# S7CAS-PLEIADES-CARTE-MERE_P07_FPGA_2.net
KiCad netlist of a schematic drawn in Altium Designer
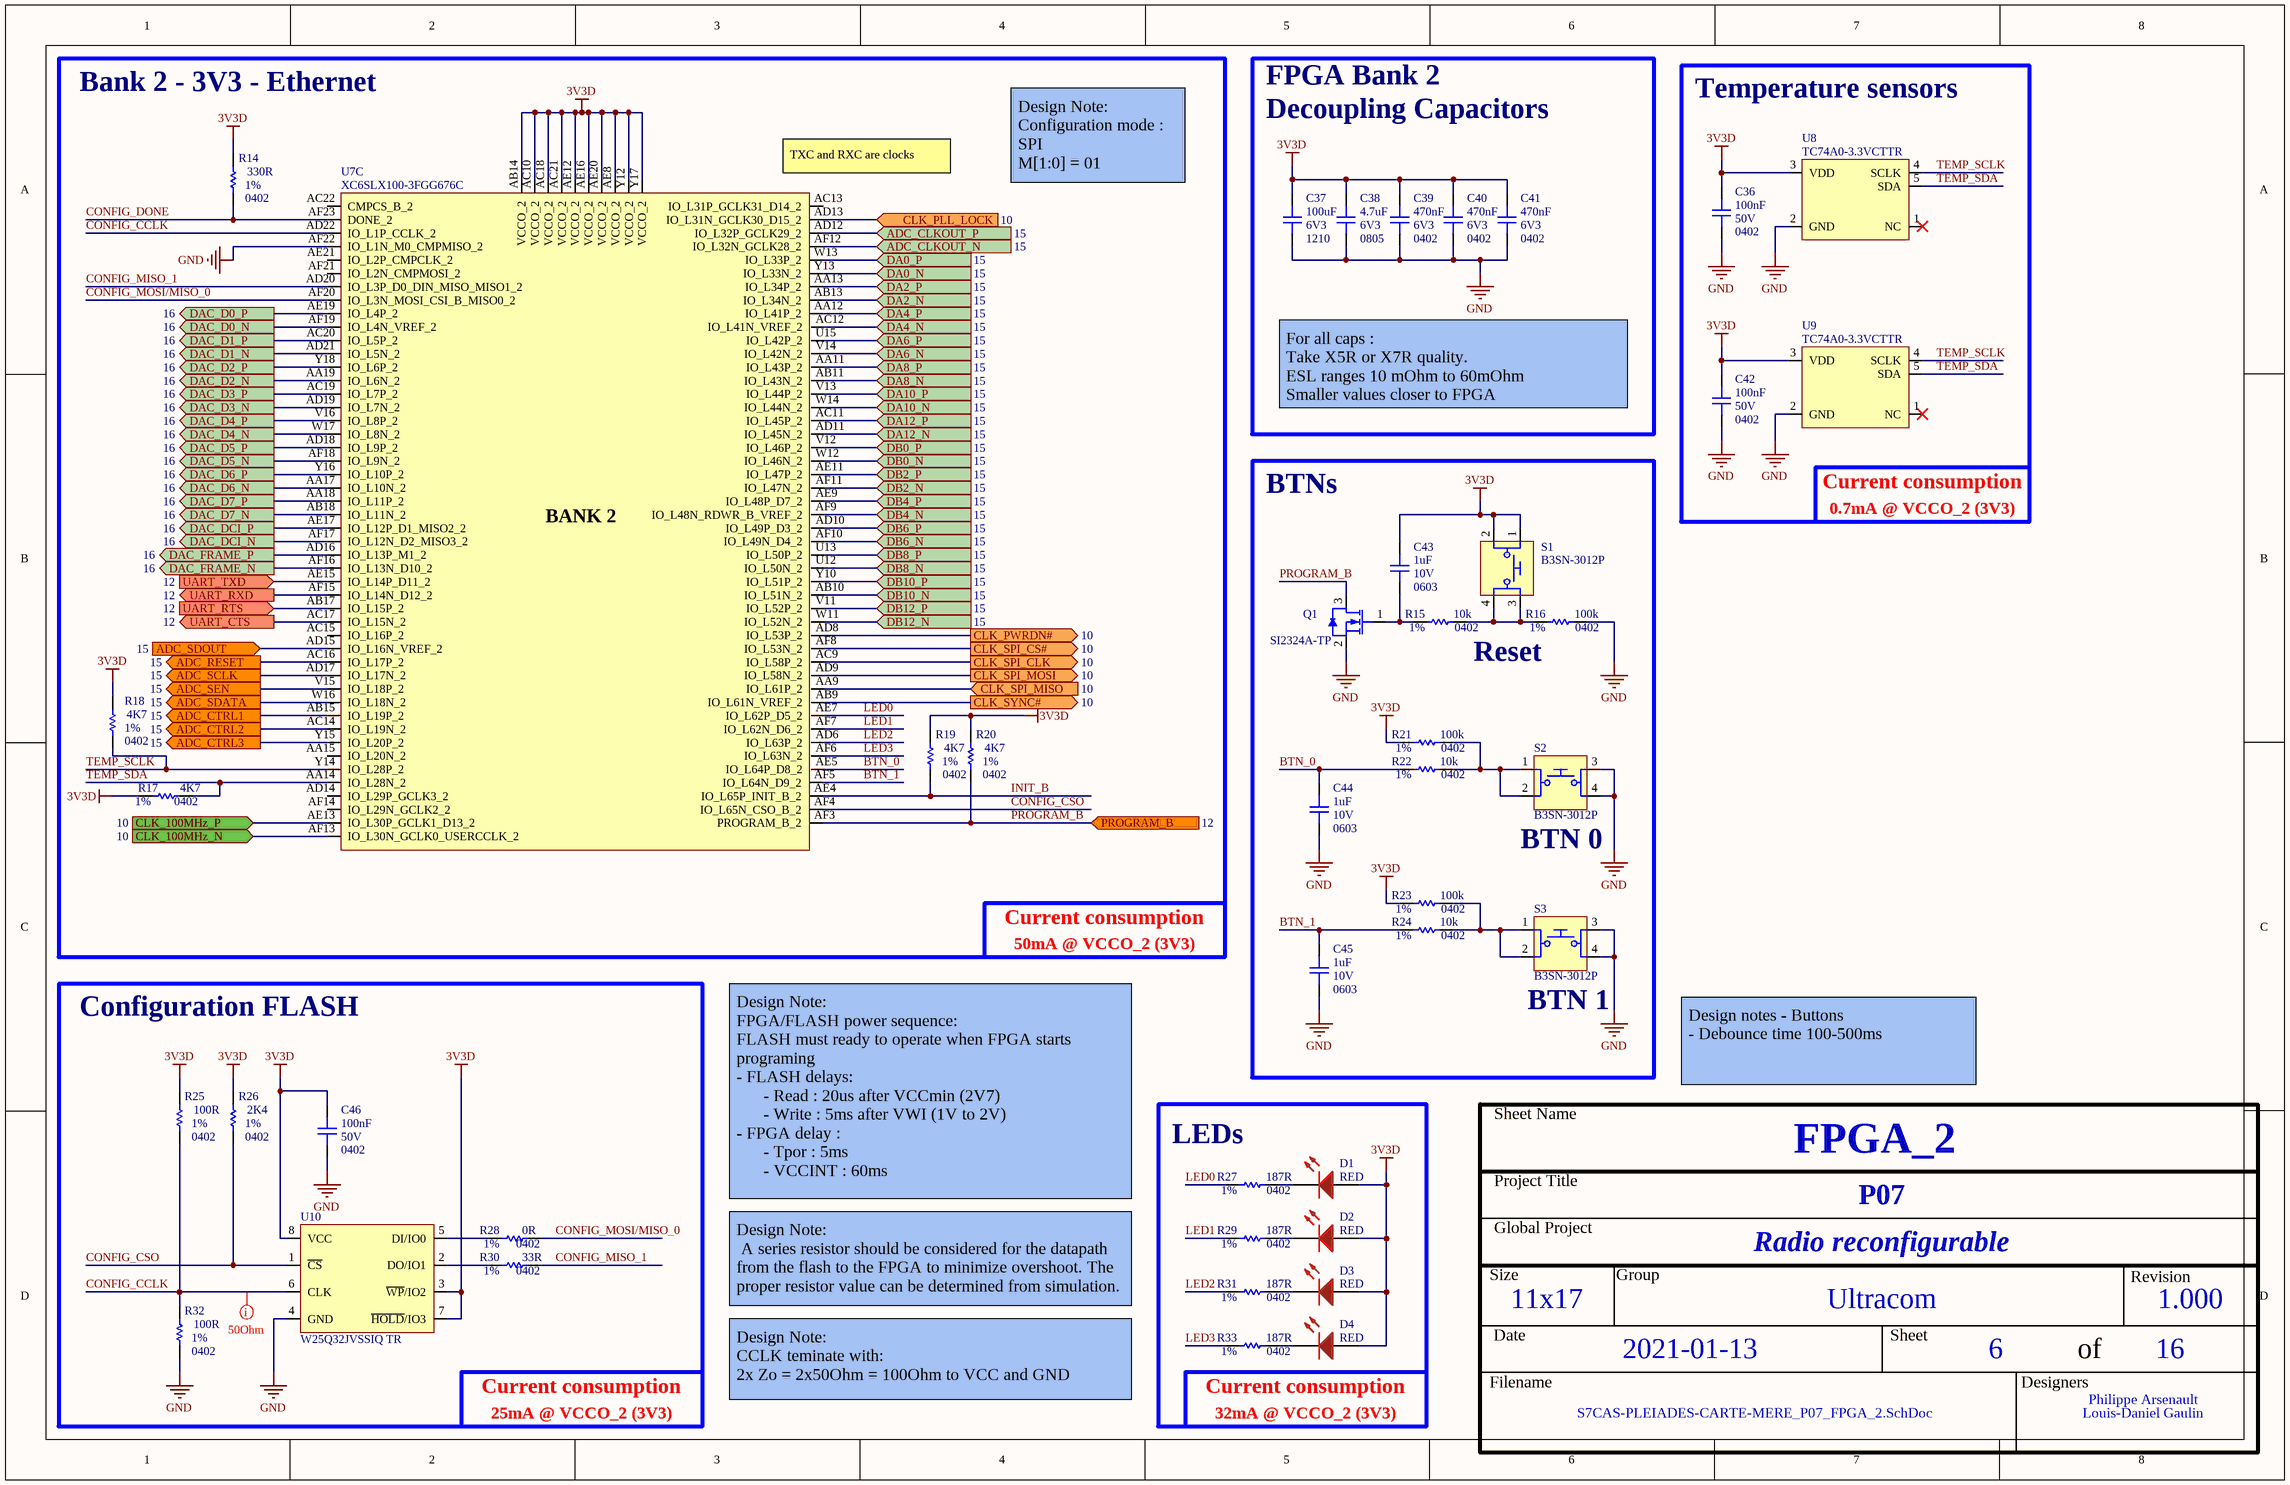
[diagram p0: S7CAS-PLEIADES-CARTE-MERE_P07_FPGA_2.SchDoc]

(export (version "E")
  (design (tool "Eeschema 10.0.6"))
  (components
    (comp (ref "C36")
      (value "100nF")
      (footprint "CAP_0402")
      (description "CAP - 0402")
      (fields
        (field (name "VOLTAGE") "50V")
        (field (name "PACKAGE") "0402")
        (field (name "CREATEDBY") "Jonathan Bouchard")
      )
      (libsource (lib "S7CAS_LIB2021") (part "CAP - 0402"))
    )
    (comp (ref "C37")
      (value "100uF")
      (footprint "CAP_1210")
      (description "CAP - 1210")
      (fields
        (field (name "VOLTAGE") "6V3")
        (field (name "PACKAGE") "1210")
        (field (name "CREATEDBY") "Jonathan Bouchard")
      )
      (libsource (lib "S7CAS_LIB2021") (part "CAP - 1210"))
    )
    (comp (ref "C38")
      (value "4.7uF")
      (footprint "CAP_0805")
      (description "CAP - 0805")
      (fields
        (field (name "VOLTAGE") "6V3")
        (field (name "PACKAGE") "0805")
        (field (name "CREATEDBY") "Jonathan Bouchard")
      )
      (libsource (lib "S7CAS_LIB2021") (part "CAP - 0805"))
    )
    (comp (ref "C39")
      (value "470nF")
      (footprint "CAP_0402")
      (description "CAP - 0402")
      (fields
        (field (name "VOLTAGE") "6V3")
        (field (name "PACKAGE") "0402")
        (field (name "CREATEDBY") "Jonathan Bouchard")
      )
      (libsource (lib "S7CAS_LIB2021") (part "CAP - 0402"))
    )
    (comp (ref "C40")
      (value "470nF")
      (footprint "CAP_0402")
      (description "CAP - 0402")
      (fields
        (field (name "VOLTAGE") "6V3")
        (field (name "PACKAGE") "0402")
        (field (name "CREATEDBY") "Jonathan Bouchard")
      )
      (libsource (lib "S7CAS_LIB2021") (part "CAP - 0402"))
    )
    (comp (ref "C41")
      (value "470nF")
      (footprint "CAP_0402")
      (description "CAP - 0402")
      (fields
        (field (name "VOLTAGE") "6V3")
        (field (name "PACKAGE") "0402")
        (field (name "CREATEDBY") "Jonathan Bouchard")
      )
      (libsource (lib "S7CAS_LIB2021") (part "CAP - 0402"))
    )
    (comp (ref "C42")
      (value "100nF")
      (footprint "CAP_0402")
      (description "CAP - 0402")
      (fields
        (field (name "VOLTAGE") "50V")
        (field (name "PACKAGE") "0402")
        (field (name "CREATEDBY") "Jonathan Bouchard")
      )
      (libsource (lib "S7CAS_LIB2021") (part "CAP - 0402"))
    )
    (comp (ref "C43")
      (value "1uF")
      (footprint "CAP_0603")
      (description "CAP - 0603")
      (fields
        (field (name "VOLTAGE") "10V")
        (field (name "PACKAGE") "0603")
        (field (name "CREATEDBY") "Jonathan Bouchard")
      )
      (libsource (lib "S7CAS_LIB2021") (part "CAP - 0603"))
    )
    (comp (ref "C44")
      (value "1uF")
      (footprint "CAP_0603")
      (description "CAP - 0603")
      (fields
        (field (name "VOLTAGE") "10V")
        (field (name "PACKAGE") "0603")
        (field (name "CREATEDBY") "Jonathan Bouchard")
      )
      (libsource (lib "S7CAS_LIB2021") (part "CAP - 0603"))
    )
    (comp (ref "C45")
      (value "1uF")
      (footprint "CAP_0603")
      (description "CAP - 0603")
      (fields
        (field (name "VOLTAGE") "10V")
        (field (name "PACKAGE") "0603")
        (field (name "CREATEDBY") "Jonathan Bouchard")
      )
      (libsource (lib "S7CAS_LIB2021") (part "CAP - 0603"))
    )
    (comp (ref "C46")
      (value "100nF")
      (footprint "CAP_0402")
      (description "CAP - 0402")
      (fields
        (field (name "VOLTAGE") "50V")
        (field (name "PACKAGE") "0402")
        (field (name "CREATEDBY") "Jonathan Bouchard")
      )
      (libsource (lib "S7CAS_LIB2021") (part "CAP - 0402"))
    )
    (comp (ref "D1")
      (value "RED")
      (footprint "LED_0603")
      (description "LED - 620nM RED 2mA - 0603")
      (fields
        (field (name "VOLTAGE") "1.8V")
        (field (name "MFG") "ROHM Semiconductor")
        (field (name "CREATEDBY") "Jonathan Bouchard")
      )
      (libsource (lib "S7CAS_LIB2021") (part "LED_SML-311UTT86"))
    )
    (comp (ref "D2")
      (value "RED")
      (footprint "LED_0603")
      (description "LED - 620nM RED 2mA - 0603")
      (fields
        (field (name "VOLTAGE") "1.8V")
        (field (name "MFG") "ROHM Semiconductor")
        (field (name "CREATEDBY") "Jonathan Bouchard")
      )
      (libsource (lib "S7CAS_LIB2021") (part "LED_SML-311UTT86"))
    )
    (comp (ref "D3")
      (value "RED")
      (footprint "LED_0603")
      (description "LED - 620nM RED 2mA - 0603")
      (fields
        (field (name "VOLTAGE") "1.8V")
        (field (name "MFG") "ROHM Semiconductor")
        (field (name "CREATEDBY") "Jonathan Bouchard")
      )
      (libsource (lib "S7CAS_LIB2021") (part "LED_SML-311UTT86"))
    )
    (comp (ref "D4")
      (value "RED")
      (footprint "LED_0603")
      (description "LED - 620nM RED 2mA - 0603")
      (fields
        (field (name "VOLTAGE") "1.8V")
        (field (name "MFG") "ROHM Semiconductor")
        (field (name "CREATEDBY") "Jonathan Bouchard")
      )
      (libsource (lib "S7CAS_LIB2021") (part "LED_SML-311UTT86"))
    )
    (comp (ref "Q1")
      (value "SI2324A-TP")
      (footprint "TRX_NMOS_SI324A-TP")
      (description "TRX - MOSFET N-CH 100V 2A - SOT-23")
      (fields (field (name "CREATEDBY/DATE") "*") (field (name "VERIFIEDBY") "*"))
      (libsource (lib "S7CAS_P07") (part "TRX_NMOS_SI2324A-TP"))
    )
    (comp (ref "R14")
      (value "330R")
      (footprint "RES_0402")
      (description "RES - 0402")
      (fields
        (field (name "VOLTAGE") "50V")
        (field (name "POWER") "1/16W")
        (field (name "PACKAGE") "0402")
        (field (name "PRECISION") "1%")
        (field (name "CREATEDBY") "Jonathan Bouchard")
      )
      (libsource (lib "S7CAS_LIB2021") (part "RES - 0402"))
    )
    (comp (ref "R15")
      (value "10k")
      (footprint "RES_0402")
      (description "RES - 0402")
      (fields
        (field (name "VOLTAGE") "50V")
        (field (name "POWER") "1/16W")
        (field (name "PACKAGE") "0402")
        (field (name "PRECISION") "1%")
        (field (name "CREATEDBY") "Jonathan Bouchard")
      )
      (libsource (lib "S7CAS_LIB2021") (part "RES - 0402"))
    )
    (comp (ref "R16")
      (value "100k")
      (footprint "RES_0402")
      (description "RES - 0402")
      (fields
        (field (name "VOLTAGE") "50V")
        (field (name "POWER") "1/16W")
        (field (name "PACKAGE") "0402")
        (field (name "PRECISION") "1%")
        (field (name "CREATEDBY") "Jonathan Bouchard")
      )
      (libsource (lib "S7CAS_LIB2021") (part "RES - 0402"))
    )
    (comp (ref "R17")
      (value "4K7")
      (footprint "RES_0402")
      (description "RES - 0402")
      (fields
        (field (name "VOLTAGE") "50V")
        (field (name "POWER") "1/16W")
        (field (name "PACKAGE") "0402")
        (field (name "PRECISION") "1%")
        (field (name "CREATEDBY") "Jonathan Bouchard")
      )
      (libsource (lib "S7CAS_LIB2021") (part "RES - 0402"))
    )
    (comp (ref "R18")
      (value "4K7")
      (footprint "RES_0402")
      (description "RES - 0402")
      (fields
        (field (name "VOLTAGE") "50V")
        (field (name "POWER") "1/16W")
        (field (name "PACKAGE") "0402")
        (field (name "PRECISION") "1%")
        (field (name "CREATEDBY") "Jonathan Bouchard")
      )
      (libsource (lib "S7CAS_LIB2021") (part "RES - 0402"))
    )
    (comp (ref "R19")
      (value "4K7")
      (footprint "RES_0402")
      (description "RES - 0402")
      (fields
        (field (name "VOLTAGE") "50V")
        (field (name "POWER") "1/16W")
        (field (name "PACKAGE") "0402")
        (field (name "PRECISION") "1%")
        (field (name "CREATEDBY") "Jonathan Bouchard")
      )
      (libsource (lib "S7CAS_LIB2021") (part "RES - 0402"))
    )
    (comp (ref "R20")
      (value "4K7")
      (footprint "RES_0402")
      (description "RES - 0402")
      (fields
        (field (name "VOLTAGE") "50V")
        (field (name "POWER") "1/16W")
        (field (name "PACKAGE") "0402")
        (field (name "PRECISION") "1%")
        (field (name "CREATEDBY") "Jonathan Bouchard")
      )
      (libsource (lib "S7CAS_LIB2021") (part "RES - 0402"))
    )
    (comp (ref "R21")
      (value "100k")
      (footprint "RES_0402")
      (description "RES - 0402")
      (fields
        (field (name "VOLTAGE") "50V")
        (field (name "POWER") "1/16W")
        (field (name "PACKAGE") "0402")
        (field (name "PRECISION") "1%")
        (field (name "CREATEDBY") "Jonathan Bouchard")
      )
      (libsource (lib "S7CAS_LIB2021") (part "RES - 0402"))
    )
    (comp (ref "R22")
      (value "10k")
      (footprint "RES_0402")
      (description "RES - 0402")
      (fields
        (field (name "VOLTAGE") "50V")
        (field (name "POWER") "1/16W")
        (field (name "PACKAGE") "0402")
        (field (name "PRECISION") "1%")
        (field (name "CREATEDBY") "Jonathan Bouchard")
      )
      (libsource (lib "S7CAS_LIB2021") (part "RES - 0402"))
    )
    (comp (ref "R23")
      (value "100k")
      (footprint "RES_0402")
      (description "RES - 0402")
      (fields
        (field (name "VOLTAGE") "50V")
        (field (name "POWER") "1/16W")
        (field (name "PACKAGE") "0402")
        (field (name "PRECISION") "1%")
        (field (name "CREATEDBY") "Jonathan Bouchard")
      )
      (libsource (lib "S7CAS_LIB2021") (part "RES - 0402"))
    )
    (comp (ref "R24")
      (value "10k")
      (footprint "RES_0402")
      (description "RES - 0402")
      (fields
        (field (name "VOLTAGE") "50V")
        (field (name "POWER") "1/16W")
        (field (name "PACKAGE") "0402")
        (field (name "PRECISION") "1%")
        (field (name "CREATEDBY") "Jonathan Bouchard")
      )
      (libsource (lib "S7CAS_LIB2021") (part "RES - 0402"))
    )
    (comp (ref "R25")
      (value "100R")
      (footprint "RES_0402")
      (description "RES - 0402")
      (fields
        (field (name "VOLTAGE") "50V")
        (field (name "POWER") "1/16W")
        (field (name "PACKAGE") "0402")
        (field (name "PRECISION") "1%")
        (field (name "CREATEDBY") "Jonathan Bouchard")
      )
      (libsource (lib "S7CAS_LIB2021") (part "RES - 0402"))
    )
    (comp (ref "R26")
      (value "2K4")
      (footprint "RES_0402")
      (description "RES - 0402")
      (fields
        (field (name "VOLTAGE") "50V")
        (field (name "POWER") "1/16W")
        (field (name "PACKAGE") "0402")
        (field (name "PRECISION") "1%")
        (field (name "CREATEDBY") "Jonathan Bouchard")
      )
      (libsource (lib "S7CAS_LIB2021") (part "RES - 0402"))
    )
    (comp (ref "R27")
      (value "187R")
      (footprint "RES_0402")
      (description "RES - 0402")
      (fields
        (field (name "VOLTAGE") "50V")
        (field (name "POWER") "1/16W")
        (field (name "PACKAGE") "0402")
        (field (name "PRECISION") "1%")
        (field (name "CREATEDBY") "Jonathan Bouchard")
      )
      (libsource (lib "S7CAS_LIB2021") (part "RES - 0402"))
    )
    (comp (ref "R28")
      (value "0R")
      (footprint "RES_0402")
      (description "RES - 0402")
      (fields
        (field (name "VOLTAGE") "50V")
        (field (name "POWER") "1/16W")
        (field (name "PACKAGE") "0402")
        (field (name "PRECISION") "1%")
        (field (name "CREATEDBY") "Jonathan Bouchard")
      )
      (libsource (lib "S7CAS_LIB2021") (part "RES - 0402"))
    )
    (comp (ref "R29")
      (value "187R")
      (footprint "RES_0402")
      (description "RES - 0402")
      (fields
        (field (name "VOLTAGE") "50V")
        (field (name "POWER") "1/16W")
        (field (name "PACKAGE") "0402")
        (field (name "PRECISION") "1%")
        (field (name "CREATEDBY") "Jonathan Bouchard")
      )
      (libsource (lib "S7CAS_LIB2021") (part "RES - 0402"))
    )
    (comp (ref "R30")
      (value "33R")
      (footprint "RES_0402")
      (description "RES - 0402")
      (fields
        (field (name "VOLTAGE") "50V")
        (field (name "POWER") "1/16W")
        (field (name "PACKAGE") "0402")
        (field (name "PRECISION") "1%")
        (field (name "CREATEDBY") "Jonathan Bouchard")
      )
      (libsource (lib "S7CAS_LIB2021") (part "RES - 0402"))
    )
    (comp (ref "R31")
      (value "187R")
      (footprint "RES_0402")
      (description "RES - 0402")
      (fields
        (field (name "VOLTAGE") "50V")
        (field (name "POWER") "1/16W")
        (field (name "PACKAGE") "0402")
        (field (name "PRECISION") "1%")
        (field (name "CREATEDBY") "Jonathan Bouchard")
      )
      (libsource (lib "S7CAS_LIB2021") (part "RES - 0402"))
    )
    (comp (ref "R32")
      (value "100R")
      (footprint "RES_0402")
      (description "RES - 0402")
      (fields
        (field (name "VOLTAGE") "50V")
        (field (name "POWER") "1/16W")
        (field (name "PACKAGE") "0402")
        (field (name "PRECISION") "1%")
        (field (name "CREATEDBY") "Jonathan Bouchard")
      )
      (libsource (lib "S7CAS_LIB2021") (part "RES - 0402"))
    )
    (comp (ref "R33")
      (value "187R")
      (footprint "RES_0402")
      (description "RES - 0402")
      (fields
        (field (name "VOLTAGE") "50V")
        (field (name "POWER") "1/16W")
        (field (name "PACKAGE") "0402")
        (field (name "PRECISION") "1%")
        (field (name "CREATEDBY") "Jonathan Bouchard")
      )
      (libsource (lib "S7CAS_LIB2021") (part "RES - 0402"))
    )
    (comp (ref "S1")
      (value "B3SN-3012P")
      (footprint "SWI_TACT_B3SN-3012P")
      (description "SWI - SWITCH TACTILE SPST-NO 0.05A 24V -SMD")
      (fields
        (field (name "CREATEDBY/DATE") "Olivier Bernard / 5/12/2017")
        (field (name "VERIFIEDBY") "Caroline Paulin / 11 juillet 2018")
      )
      (libsource (lib "") (part "SWI_TACT_B3SN-3012P_1_1"))
    )
    (comp (ref "S2")
      (value "B3SN-3012P")
      (footprint "SWI_TACT_B3SN-3012P")
      (description "SWI - SWITCH TACTILE SPST-NO 0.05A 24V -SMD")
      (fields
        (field (name "CREATEDBY/DATE") "Olivier Bernard / 5/12/2017")
        (field (name "VERIFIEDBY") "Caroline Paulin / 11 juillet 2018")
      )
      (libsource (lib "S7CAS_LIB2021") (part "SWI_TACT_B3SN-3012P_1"))
    )
    (comp (ref "S3")
      (value "B3SN-3012P")
      (footprint "SWI_TACT_B3SN-3012P")
      (description "SWI - SWITCH TACTILE SPST-NO 0.05A 24V -SMD")
      (fields
        (field (name "CREATEDBY/DATE") "Olivier Bernard / 5/12/2017")
        (field (name "VERIFIEDBY") "Caroline Paulin / 11 juillet 2018")
      )
      (libsource (lib "S7CAS_LIB2021") (part "SWI_TACT_B3SN-3012P_1"))
    )
    (comp (ref "U7")
      (value "XC6SLX100-3FGG676C")
      (footprint "FPGA_XILINX_FGG676")
      (description "FPGA - XILINX SPARTAN 6 480 I/O - BGA-676")
      (fields
        (field (name "VOLTAGE") "1.14 V ~ 1.26 V")
        (field (name "MFG") "Xilinx")
        (field (name "CREATEDBY") "Jonathan Bouchard")
      )
      (libsource (lib "S7CAS_LIB2021") (part "FPGA_XC6SLX100-3FGG676C"))
    )
    (comp (ref "U8")
      (value "TC74A0-3.3VCTTR")
      (footprint "SEN_TEMP_TC74A0-3.3VCTTR")
      (description "SENS - TEMPERATURE SENSOR I2C/SMBUS - SOT23-5")
      (fields
        (field (name "VOLTAGE") "2.7 V ~ 5.5 V")
        (field (name "MFG") "Microchip")
        (field (name "CREATEDBY") "Jonathan Bouchard")
      )
      (libsource (lib "S7CAS_LIB2021") (part "SENS_TEMP_TC74A0-3.3VCTTR"))
    )
    (comp (ref "U9")
      (value "TC74A0-3.3VCTTR")
      (footprint "SEN_TEMP_TC74A0-3.3VCTTR")
      (description "SENS - TEMPERATURE SENSOR I2C/SMBUS - SOT23-5")
      (fields
        (field (name "VOLTAGE") "2.7 V ~ 5.5 V")
        (field (name "MFG") "Microchip")
        (field (name "CREATEDBY") "Jonathan Bouchard")
      )
      (libsource (lib "S7CAS_LIB2021") (part "SENS_TEMP_TC74A0-3.3VCTTR"))
    )
    (comp (ref "U10")
      (value "W25Q32JVSSIQ TR")
      (footprint "MEM_FLASH_W25Q32JVSSIQ TR")
      (description "MEM - FLASH NOR 32Mb 133MHZ - 8-SOIC")
      (fields
        (field (name "VOLTAGE") "2.7 V ~ 3.6 V")
        (field (name "MFG") "Winbond Electronics")
        (field (name "CREATEDBY") "Louis-Daniel Gaulin")
      )
      (libsource (lib "S7CAS_P07") (part "MEM_FLASH_W25Q32JVSSIQ TR"))
    )
  )
  (nets
    (net (code "1") (name "/ADC_CLKOUT_N") (class "Default")
      (node (ref "U7") (pin "AF12") (pinfunction "IO_L32N_GCLK28_2_AF12") (pintype "passive"))
    )
    (net (code "2") (name "/ADC_CLKOUT_P") (class "Default")
      (node (ref "U7") (pin "AD12") (pinfunction "IO_L32P_GCLK29_2_AD12") (pintype "passive"))
    )
    (net (code "3") (name "/ADC_CTRL1") (class "Default")
      (node (ref "U7") (pin "AB15") (pinfunction "IO_L19P_2_AB15") (pintype "passive"))
    )
    (net (code "4") (name "/ADC_CTRL2") (class "Default")
      (node (ref "U7") (pin "AC14") (pinfunction "IO_L19N_2_AC14") (pintype "passive"))
    )
    (net (code "5") (name "/ADC_CTRL3") (class "Default")
      (node (ref "U7") (pin "Y15") (pinfunction "IO_L20P_2_Y15") (pintype "passive"))
    )
    (net (code "6") (name "/ADC_RESET") (class "Default")
      (node (ref "U7") (pin "AC16") (pinfunction "IO_L17P_2_AC16") (pintype "passive"))
    )
    (net (code "7") (name "/ADC_SCLK") (class "Default")
      (node (ref "U7") (pin "AD17") (pinfunction "IO_L17N_2_AD17") (pintype "passive"))
    )
    (net (code "8") (name "/ADC_SDATA") (class "Default")
      (node (ref "U7") (pin "W16") (pinfunction "IO_L18N_2_W16") (pintype "passive"))
    )
    (net (code "9") (name "/ADC_SDOUT") (class "Default")
      (node (ref "U7") (pin "AD15") (pinfunction "IO_L16N_VREF_2_AD15") (pintype "passive"))
    )
    (net (code "10") (name "/ADC_SEN") (class "Default")
      (node (ref "U7") (pin "V15") (pinfunction "IO_L18P_2_V15") (pintype "passive"))
    )
    (net (code "11") (name "/BTN_0") (class "Default")
      (node (ref "C44") (pin "2") (pinfunction "2_2") (pintype "passive"))
      (node (ref "R22") (pin "1") (pinfunction "1_1") (pintype "passive"))
      (node (ref "U7") (pin "AE5") (pinfunction "IO_L64P_D8_2_AE5") (pintype "passive"))
    )
    (net (code "12") (name "/BTN_1") (class "Default")
      (node (ref "C45") (pin "2") (pinfunction "2_2") (pintype "passive"))
      (node (ref "R24") (pin "1") (pinfunction "1_1") (pintype "passive"))
      (node (ref "U7") (pin "AF5") (pinfunction "IO_L64N_D9_2_AF5") (pintype "passive"))
    )
    (net (code "13") (name "/CLK_100MHz_N") (class "Default")
      (node (ref "U7") (pin "AF13") (pinfunction "IO_L30N_GCLK0_USERCCLK_2_AF13") (pintype "passive"))
    )
    (net (code "14") (name "/CLK_100MHz_P") (class "Default")
      (node (ref "U7") (pin "AE13") (pinfunction "IO_L30P_GCLK1_D13_2_AE13") (pintype "passive"))
    )
    (net (code "15") (name "/CLK_PLL_LOCK") (class "Default")
      (node (ref "U7") (pin "AD13") (pinfunction "IO_L31N_GCLK30_D15_2_AD13") (pintype "passive"))
    )
    (net (code "16") (name "/CLK_PWRDN#") (class "Default")
      (node (ref "U7") (pin "AD8") (pinfunction "IO_L53P_2_AD8") (pintype "passive"))
    )
    (net (code "17") (name "/CLK_SPI_CLK") (class "Default")
      (node (ref "U7") (pin "AC9") (pinfunction "IO_L58P_2_AC9") (pintype "passive"))
    )
    (net (code "18") (name "/CLK_SPI_CS#") (class "Default")
      (node (ref "U7") (pin "AF8") (pinfunction "IO_L53N_2_AF8") (pintype "passive"))
    )
    (net (code "19") (name "/CLK_SPI_MISO") (class "Default")
      (node (ref "U7") (pin "AA9") (pinfunction "IO_L61P_2_AA9") (pintype "passive"))
    )
    (net (code "20") (name "/CLK_SPI_MOSI") (class "Default")
      (node (ref "U7") (pin "AD9") (pinfunction "IO_L58N_2_AD9") (pintype "passive"))
    )
    (net (code "21") (name "/CLK_SYNC#") (class "Default")
      (node (ref "U7") (pin "AB9") (pinfunction "IO_L61N_VREF_2_AB9") (pintype "passive"))
    )
    (net (code "22") (name "/CONFIG_CCLK") (class "Default")
      (node (ref "R25") (pin "1") (pinfunction "1_1") (pintype "passive"))
      (node (ref "R32") (pin "2") (pinfunction "2_2") (pintype "passive"))
      (node (ref "U10") (pin "6") (pinfunction "CLK_6") (pintype "passive"))
      (node (ref "U7") (pin "AD22") (pinfunction "IO_L1P_CCLK_2_AD22") (pintype "passive"))
    )
    (net (code "23") (name "/CONFIG_CSO") (class "Default")
      (node (ref "R26") (pin "1") (pinfunction "1_1") (pintype "passive"))
      (node (ref "U10") (pin "1") (pinfunction "CS_1") (pintype "passive"))
      (node (ref "U7") (pin "AF4") (pinfunction "IO_L65N_CSO_B_2_AF4") (pintype "passive"))
    )
    (net (code "24") (name "/CONFIG_DONE") (class "Default")
      (node (ref "R14") (pin "1") (pinfunction "1_1") (pintype "passive"))
      (node (ref "U7") (pin "AF23") (pinfunction "DONE_2_AF23") (pintype "passive"))
    )
    (net (code "25") (name "/CONFIG_MISO_1") (class "Default")
      (node (ref "R30") (pin "1") (pinfunction "1_1") (pintype "passive"))
      (node (ref "U7") (pin "AD20") (pinfunction "IO_L3P_D0_DIN_MISO_MISO1_2_AD20") (pintype "passive"))
    )
    (net (code "26") (name "/CONFIG_MOSI{slash}MISO_0") (class "Default")
      (node (ref "R28") (pin "1") (pinfunction "1_1") (pintype "passive"))
      (node (ref "U7") (pin "AF20") (pinfunction "IO_L3N_MOSI_CSI_B_MISO0_2_AF20") (pintype "passive"))
    )
    (net (code "27") (name "/DA0_N") (class "Default")
      (node (ref "U7") (pin "Y13") (pinfunction "IO_L33N_2_Y13") (pintype "passive"))
    )
    (net (code "28") (name "/DA0_P") (class "Default")
      (node (ref "U7") (pin "W13") (pinfunction "IO_L33P_2_W13") (pintype "passive"))
    )
    (net (code "29") (name "/DA2_N") (class "Default")
      (node (ref "U7") (pin "AB13") (pinfunction "IO_L34N_2_AB13") (pintype "passive"))
    )
    (net (code "30") (name "/DA2_P") (class "Default")
      (node (ref "U7") (pin "AA13") (pinfunction "IO_L34P_2_AA13") (pintype "passive"))
    )
    (net (code "31") (name "/DA4_N") (class "Default")
      (node (ref "U7") (pin "AC12") (pinfunction "IO_L41N_VREF_2_AC12") (pintype "passive"))
    )
    (net (code "32") (name "/DA4_P") (class "Default")
      (node (ref "U7") (pin "AA12") (pinfunction "IO_L41P_2_AA12") (pintype "passive"))
    )
    (net (code "33") (name "/DA6_N") (class "Default")
      (node (ref "U7") (pin "V14") (pinfunction "IO_L42N_2_V14") (pintype "passive"))
    )
    (net (code "34") (name "/DA6_P") (class "Default")
      (node (ref "U7") (pin "U15") (pinfunction "IO_L42P_2_U15") (pintype "passive"))
    )
    (net (code "35") (name "/DA8_N") (class "Default")
      (node (ref "U7") (pin "AB11") (pinfunction "IO_L43N_2_AB11") (pintype "passive"))
    )
    (net (code "36") (name "/DA8_P") (class "Default")
      (node (ref "U7") (pin "AA11") (pinfunction "IO_L43P_2_AA11") (pintype "passive"))
    )
    (net (code "37") (name "/DA10_N") (class "Default")
      (node (ref "U7") (pin "W14") (pinfunction "IO_L44N_2_W14") (pintype "passive"))
    )
    (net (code "38") (name "/DA10_P") (class "Default")
      (node (ref "U7") (pin "V13") (pinfunction "IO_L44P_2_V13") (pintype "passive"))
    )
    (net (code "39") (name "/DA12_N") (class "Default")
      (node (ref "U7") (pin "AD11") (pinfunction "IO_L45N_2_AD11") (pintype "passive"))
    )
    (net (code "40") (name "/DA12_P") (class "Default")
      (node (ref "U7") (pin "AC11") (pinfunction "IO_L45P_2_AC11") (pintype "passive"))
    )
    (net (code "41") (name "/DAC_D0_N") (class "Default")
      (node (ref "U7") (pin "AF19") (pinfunction "IO_L4N_VREF_2_AF19") (pintype "passive"))
    )
    (net (code "42") (name "/DAC_D0_P") (class "Default")
      (node (ref "U7") (pin "AE19") (pinfunction "IO_L4P_2_AE19") (pintype "passive"))
    )
    (net (code "43") (name "/DAC_D1_N") (class "Default")
      (node (ref "U7") (pin "AD21") (pinfunction "IO_L5N_2_AD21") (pintype "passive"))
    )
    (net (code "44") (name "/DAC_D1_P") (class "Default")
      (node (ref "U7") (pin "AC20") (pinfunction "IO_L5P_2_AC20") (pintype "passive"))
    )
    (net (code "45") (name "/DAC_D2_N") (class "Default")
      (node (ref "U7") (pin "AA19") (pinfunction "IO_L6N_2_AA19") (pintype "passive"))
    )
    (net (code "46") (name "/DAC_D2_P") (class "Default")
      (node (ref "U7") (pin "Y18") (pinfunction "IO_L6P_2_Y18") (pintype "passive"))
    )
    (net (code "47") (name "/DAC_D3_N") (class "Default")
      (node (ref "U7") (pin "AD19") (pinfunction "IO_L7N_2_AD19") (pintype "passive"))
    )
    (net (code "48") (name "/DAC_D3_P") (class "Default")
      (node (ref "U7") (pin "AC19") (pinfunction "IO_L7P_2_AC19") (pintype "passive"))
    )
    (net (code "49") (name "/DAC_D4_N") (class "Default")
      (node (ref "U7") (pin "W17") (pinfunction "IO_L8N_2_W17") (pintype "passive"))
    )
    (net (code "50") (name "/DAC_D4_P") (class "Default")
      (node (ref "U7") (pin "V16") (pinfunction "IO_L8P_2_V16") (pintype "passive"))
    )
    (net (code "51") (name "/DAC_D5_N") (class "Default")
      (node (ref "U7") (pin "AF18") (pinfunction "IO_L9N_2_AF18") (pintype "passive"))
    )
    (net (code "52") (name "/DAC_D5_P") (class "Default")
      (node (ref "U7") (pin "AD18") (pinfunction "IO_L9P_2_AD18") (pintype "passive"))
    )
    (net (code "53") (name "/DAC_D6_N") (class "Default")
      (node (ref "U7") (pin "AA17") (pinfunction "IO_L10N_2_AA17") (pintype "passive"))
    )
    (net (code "54") (name "/DAC_D6_P") (class "Default")
      (node (ref "U7") (pin "Y16") (pinfunction "IO_L10P_2_Y16") (pintype "passive"))
    )
    (net (code "55") (name "/DAC_D7_N") (class "Default")
      (node (ref "U7") (pin "AB18") (pinfunction "IO_L11N_2_AB18") (pintype "passive"))
    )
    (net (code "56") (name "/DAC_D7_P") (class "Default")
      (node (ref "U7") (pin "AA18") (pinfunction "IO_L11P_2_AA18") (pintype "passive"))
    )
    (net (code "57") (name "/DAC_DCI_N") (class "Default")
      (node (ref "U7") (pin "AF17") (pinfunction "IO_L12N_D2_MISO3_2_AF17") (pintype "passive"))
    )
    (net (code "58") (name "/DAC_DCI_P") (class "Default")
      (node (ref "U7") (pin "AE17") (pinfunction "IO_L12P_D1_MISO2_2_AE17") (pintype "passive"))
    )
    (net (code "59") (name "/DAC_FRAME_N") (class "Default")
      (node (ref "U7") (pin "AF16") (pinfunction "IO_L13N_D10_2_AF16") (pintype "passive"))
    )
    (net (code "60") (name "/DAC_FRAME_P") (class "Default")
      (node (ref "U7") (pin "AD16") (pinfunction "IO_L13P_M1_2_AD16") (pintype "passive"))
    )
    (net (code "61") (name "/DB0_N") (class "Default")
      (node (ref "U7") (pin "W12") (pinfunction "IO_L46N_2_W12") (pintype "passive"))
    )
    (net (code "62") (name "/DB0_P") (class "Default")
      (node (ref "U7") (pin "V12") (pinfunction "IO_L46P_2_V12") (pintype "passive"))
    )
    (net (code "63") (name "/DB2_N") (class "Default")
      (node (ref "U7") (pin "AF11") (pinfunction "IO_L47N_2_AF11") (pintype "passive"))
    )
    (net (code "64") (name "/DB2_P") (class "Default")
      (node (ref "U7") (pin "AE11") (pinfunction "IO_L47P_2_AE11") (pintype "passive"))
    )
    (net (code "65") (name "/DB4_N") (class "Default")
      (node (ref "U7") (pin "AF9") (pinfunction "IO_L48N_RDWR_B_VREF_2_AF9") (pintype "passive"))
    )
    (net (code "66") (name "/DB4_P") (class "Default")
      (node (ref "U7") (pin "AE9") (pinfunction "IO_L48P_D7_2_AE9") (pintype "passive"))
    )
    (net (code "67") (name "/DB6_N") (class "Default")
      (node (ref "U7") (pin "AF10") (pinfunction "IO_L49N_D4_2_AF10") (pintype "passive"))
    )
    (net (code "68") (name "/DB6_P") (class "Default")
      (node (ref "U7") (pin "AD10") (pinfunction "IO_L49P_D3_2_AD10") (pintype "passive"))
    )
    (net (code "69") (name "/DB8_N") (class "Default")
      (node (ref "U7") (pin "U12") (pinfunction "IO_L50N_2_U12") (pintype "passive"))
    )
    (net (code "70") (name "/DB8_P") (class "Default")
      (node (ref "U7") (pin "U13") (pinfunction "IO_L50P_2_U13") (pintype "passive"))
    )
    (net (code "71") (name "/DB10_N") (class "Default")
      (node (ref "U7") (pin "AB10") (pinfunction "IO_L51N_2_AB10") (pintype "passive"))
    )
    (net (code "72") (name "/DB10_P") (class "Default")
      (node (ref "U7") (pin "Y10") (pinfunction "IO_L51P_2_Y10") (pintype "passive"))
    )
    (net (code "73") (name "/DB12_N") (class "Default")
      (node (ref "U7") (pin "W11") (pinfunction "IO_L52N_2_W11") (pintype "passive"))
    )
    (net (code "74") (name "/DB12_P") (class "Default")
      (node (ref "U7") (pin "V11") (pinfunction "IO_L52P_2_V11") (pintype "passive"))
    )
    (net (code "75") (name "/INIT_B") (class "Default")
      (node (ref "R19") (pin "1") (pinfunction "1_1") (pintype "passive"))
      (node (ref "U7") (pin "AE4") (pinfunction "IO_L65P_INIT_B_2_AE4") (pintype "passive"))
    )
    (net (code "76") (name "/LED0") (class "Default")
      (node (ref "R27") (pin "1") (pinfunction "1_1") (pintype "passive"))
      (node (ref "U7") (pin "AE7") (pinfunction "IO_L62P_D5_2_AE7") (pintype "passive"))
    )
    (net (code "77") (name "/LED1") (class "Default")
      (node (ref "R29") (pin "1") (pinfunction "1_1") (pintype "passive"))
      (node (ref "U7") (pin "AF7") (pinfunction "IO_L62N_D6_2_AF7") (pintype "passive"))
    )
    (net (code "78") (name "/LED2") (class "Default")
      (node (ref "R31") (pin "1") (pinfunction "1_1") (pintype "passive"))
      (node (ref "U7") (pin "AD6") (pinfunction "IO_L63P_2_AD6") (pintype "passive"))
    )
    (net (code "79") (name "/LED3") (class "Default")
      (node (ref "R33") (pin "1") (pinfunction "1_1") (pintype "passive"))
      (node (ref "U7") (pin "AF6") (pinfunction "IO_L63N_2_AF6") (pintype "passive"))
    )
    (net (code "80") (name "/PROGRAM_B") (class "Default")
      (node (ref "Q1") (pin "3") (pinfunction "D_3") (pintype "passive"))
      (node (ref "R20") (pin "1") (pinfunction "1_1") (pintype "passive"))
      (node (ref "U7") (pin "AF3") (pinfunction "PROGRAM_B_2_AF3") (pintype "passive"))
    )
    (net (code "81") (name "/TEMP_SCLK") (class "Default")
      (node (ref "R18") (pin "1") (pinfunction "1_1") (pintype "passive"))
      (node (ref "U7") (pin "Y14") (pinfunction "IO_L28P_2_Y14") (pintype "passive"))
      (node (ref "U8") (pin "4") (pinfunction "SCLK_4") (pintype "passive"))
      (node (ref "U9") (pin "4") (pinfunction "SCLK_4") (pintype "passive"))
    )
    (net (code "82") (name "/TEMP_SDA") (class "Default")
      (node (ref "R17") (pin "2") (pinfunction "2_2") (pintype "passive"))
      (node (ref "U7") (pin "AA14") (pinfunction "IO_L28N_2_AA14") (pintype "passive"))
      (node (ref "U8") (pin "5") (pinfunction "SDA_5") (pintype "passive"))
      (node (ref "U9") (pin "5") (pinfunction "SDA_5") (pintype "passive"))
    )
    (net (code "83") (name "/UART_CTS") (class "Default")
      (node (ref "U7") (pin "AC17") (pinfunction "IO_L15N_2_AC17") (pintype "passive"))
    )
    (net (code "84") (name "/UART_RTS") (class "Default")
      (node (ref "U7") (pin "AB17") (pinfunction "IO_L15P_2_AB17") (pintype "passive"))
    )
    (net (code "85") (name "/UART_RXD") (class "Default")
      (node (ref "U7") (pin "AF15") (pinfunction "IO_L14N_D12_2_AF15") (pintype "passive"))
    )
    (net (code "86") (name "/UART_TXD") (class "Default")
      (node (ref "U7") (pin "AE15") (pinfunction "IO_L14P_D11_2_AE15") (pintype "passive"))
    )
    (net (code "87") (name "3V3D") (class "Default")
      (node (ref "C36") (pin "2") (pinfunction "2_2") (pintype "passive"))
      (node (ref "C37") (pin "2") (pinfunction "2_2") (pintype "passive"))
      (node (ref "C38") (pin "2") (pinfunction "2_2") (pintype "passive"))
      (node (ref "C39") (pin "2") (pinfunction "2_2") (pintype "passive"))
      (node (ref "C40") (pin "2") (pinfunction "2_2") (pintype "passive"))
      (node (ref "C41") (pin "2") (pinfunction "2_2") (pintype "passive"))
      (node (ref "C42") (pin "2") (pinfunction "2_2") (pintype "passive"))
      (node (ref "C43") (pin "2") (pinfunction "2_2") (pintype "passive"))
      (node (ref "C46") (pin "2") (pinfunction "2_2") (pintype "passive"))
      (node (ref "D1") (pin "A") (pinfunction "A_A") (pintype "passive"))
      (node (ref "D2") (pin "A") (pinfunction "A_A") (pintype "passive"))
      (node (ref "D3") (pin "A") (pinfunction "A_A") (pintype "passive"))
      (node (ref "D4") (pin "A") (pinfunction "A_A") (pintype "passive"))
      (node (ref "R14") (pin "2") (pinfunction "2_2") (pintype "passive"))
      (node (ref "R17") (pin "1") (pinfunction "1_1") (pintype "passive"))
      (node (ref "R18") (pin "2") (pinfunction "2_2") (pintype "passive"))
      (node (ref "R19") (pin "2") (pinfunction "2_2") (pintype "passive"))
      (node (ref "R20") (pin "2") (pinfunction "2_2") (pintype "passive"))
      (node (ref "R21") (pin "1") (pinfunction "1_1") (pintype "passive"))
      (node (ref "R23") (pin "1") (pinfunction "1_1") (pintype "passive"))
      (node (ref "R25") (pin "2") (pinfunction "2_2") (pintype "passive"))
      (node (ref "R26") (pin "2") (pinfunction "2_2") (pintype "passive"))
      (node (ref "S1") (pin "1") (pinfunction "1_1") (pintype "passive"))
      (node (ref "S1") (pin "2") (pinfunction "2_2") (pintype "passive"))
      (node (ref "U10") (pin "3") (pinfunction "~{WP}/IO2_3") (pintype "passive"))
      (node (ref "U10") (pin "7") (pinfunction "~{HOLD}/IO3_7") (pintype "passive"))
      (node (ref "U10") (pin "8") (pinfunction "VCC_8") (pintype "passive"))
      (node (ref "U7") (pin "AB14") (pinfunction "VCCO_2_AB14") (pintype "passive"))
      (node (ref "U7") (pin "AC10") (pinfunction "VCCO_2_AC10") (pintype "passive"))
      (node (ref "U7") (pin "AC18") (pinfunction "VCCO_2_AC18") (pintype "passive"))
      (node (ref "U7") (pin "AC21") (pinfunction "VCCO_2_AC21") (pintype "passive"))
      (node (ref "U7") (pin "AE12") (pinfunction "VCCO_2_AE12") (pintype "passive"))
      (node (ref "U7") (pin "AE16") (pinfunction "VCCO_2_AE16") (pintype "passive"))
      (node (ref "U7") (pin "AE20") (pinfunction "VCCO_2_AE20") (pintype "passive"))
      (node (ref "U7") (pin "AE8") (pinfunction "VCCO_2_AE8") (pintype "passive"))
      (node (ref "U7") (pin "Y12") (pinfunction "VCCO_2_Y12") (pintype "passive"))
      (node (ref "U7") (pin "Y17") (pinfunction "VCCO_2_Y17") (pintype "passive"))
      (node (ref "U8") (pin "3") (pinfunction "VDD_3") (pintype "passive"))
      (node (ref "U9") (pin "3") (pinfunction "VDD_3") (pintype "passive"))
    )
    (net (code "88") (name "GND") (class "Default")
      (node (ref "C36") (pin "1") (pinfunction "1_1") (pintype "passive"))
      (node (ref "C37") (pin "1") (pinfunction "1_1") (pintype "passive"))
      (node (ref "C38") (pin "1") (pinfunction "1_1") (pintype "passive"))
      (node (ref "C39") (pin "1") (pinfunction "1_1") (pintype "passive"))
      (node (ref "C40") (pin "1") (pinfunction "1_1") (pintype "passive"))
      (node (ref "C41") (pin "1") (pinfunction "1_1") (pintype "passive"))
      (node (ref "C42") (pin "1") (pinfunction "1_1") (pintype "passive"))
      (node (ref "C44") (pin "1") (pinfunction "1_1") (pintype "passive"))
      (node (ref "C45") (pin "1") (pinfunction "1_1") (pintype "passive"))
      (node (ref "C46") (pin "1") (pinfunction "1_1") (pintype "passive"))
      (node (ref "Q1") (pin "2") (pinfunction "S_2") (pintype "passive"))
      (node (ref "R16") (pin "2") (pinfunction "2_2") (pintype "passive"))
      (node (ref "R32") (pin "1") (pinfunction "1_1") (pintype "passive"))
      (node (ref "S2") (pin "3") (pinfunction "3_3") (pintype "passive"))
      (node (ref "S2") (pin "4") (pinfunction "4_4") (pintype "passive"))
      (node (ref "S3") (pin "3") (pinfunction "3_3") (pintype "passive"))
      (node (ref "S3") (pin "4") (pinfunction "4_4") (pintype "passive"))
      (node (ref "U10") (pin "4") (pinfunction "GND_4") (pintype "passive"))
      (node (ref "U7") (pin "AF22") (pinfunction "IO_L1N_M0_CMPMISO_2_AF22") (pintype "passive"))
      (node (ref "U8") (pin "2") (pinfunction "GND_2") (pintype "passive"))
      (node (ref "U9") (pin "2") (pinfunction "GND_2") (pintype "passive"))
    )
    (net (code "89") (name "Net-(D1-PadK)") (class "Default")
      (node (ref "D1") (pin "K") (pinfunction "K_K") (pintype "passive"))
      (node (ref "R27") (pin "2") (pinfunction "2_2") (pintype "passive"))
    )
    (net (code "90") (name "Net-(D2-PadK)") (class "Default")
      (node (ref "D2") (pin "K") (pinfunction "K_K") (pintype "passive"))
      (node (ref "R29") (pin "2") (pinfunction "2_2") (pintype "passive"))
    )
    (net (code "91") (name "Net-(D3-PadK)") (class "Default")
      (node (ref "D3") (pin "K") (pinfunction "K_K") (pintype "passive"))
      (node (ref "R31") (pin "2") (pinfunction "2_2") (pintype "passive"))
    )
    (net (code "92") (name "Net-(D4-PadK)") (class "Default")
      (node (ref "D4") (pin "K") (pinfunction "K_K") (pintype "passive"))
      (node (ref "R33") (pin "2") (pinfunction "2_2") (pintype "passive"))
    )
    (net (code "93") (name "Net-(Q1-G)") (class "Default")
      (node (ref "C43") (pin "1") (pinfunction "1_1") (pintype "passive"))
      (node (ref "Q1") (pin "1") (pinfunction "G_1") (pintype "passive"))
      (node (ref "R15") (pin "1") (pinfunction "1_1") (pintype "passive"))
    )
    (net (code "94") (name "Net-(R15-Pad2)") (class "Default")
      (node (ref "R15") (pin "2") (pinfunction "2_2") (pintype "passive"))
      (node (ref "R16") (pin "1") (pinfunction "1_1") (pintype "passive"))
      (node (ref "S1") (pin "3") (pinfunction "3_3") (pintype "passive"))
      (node (ref "S1") (pin "4") (pinfunction "4_4") (pintype "passive"))
    )
    (net (code "95") (name "Net-(R21-Pad2)") (class "Default")
      (node (ref "R21") (pin "2") (pinfunction "2_2") (pintype "passive"))
      (node (ref "R22") (pin "2") (pinfunction "2_2") (pintype "passive"))
      (node (ref "S2") (pin "1") (pinfunction "1_1") (pintype "passive"))
      (node (ref "S2") (pin "2") (pinfunction "2_2") (pintype "passive"))
    )
    (net (code "96") (name "Net-(R23-Pad2)") (class "Default")
      (node (ref "R23") (pin "2") (pinfunction "2_2") (pintype "passive"))
      (node (ref "R24") (pin "2") (pinfunction "2_2") (pintype "passive"))
      (node (ref "S3") (pin "1") (pinfunction "1_1") (pintype "passive"))
      (node (ref "S3") (pin "2") (pinfunction "2_2") (pintype "passive"))
    )
    (net (code "97") (name "Net-(U10-DI{slash}IO0)") (class "Default")
      (node (ref "R28") (pin "2") (pinfunction "2_2") (pintype "passive"))
      (node (ref "U10") (pin "5") (pinfunction "DI/IO0_5") (pintype "passive"))
    )
    (net (code "98") (name "Net-(U10-DO{slash}IO1)") (class "Default")
      (node (ref "R30") (pin "2") (pinfunction "2_2") (pintype "passive"))
      (node (ref "U10") (pin "2") (pinfunction "DO/IO1_2") (pintype "passive"))
    )
    (net (code "99") (name "unconnected-(U7C-CMPCS_B_2-PadAC22)") (class "Default")
      (node (ref "U7") (pin "AC22") (pinfunction "CMPCS_B_2_AC22") (pintype "passive"))
    )
    (net (code "100") (name "unconnected-(U7C-IO_L2N_CMPMOSI_2-PadAF21)") (class "Default")
      (node (ref "U7") (pin "AF21") (pinfunction "IO_L2N_CMPMOSI_2_AF21") (pintype "passive"))
    )
    (net (code "101") (name "unconnected-(U7C-IO_L2P_CMPCLK_2-PadAE21)") (class "Default")
      (node (ref "U7") (pin "AE21") (pinfunction "IO_L2P_CMPCLK_2_AE21") (pintype "passive"))
    )
    (net (code "102") (name "unconnected-(U7C-IO_L16P_2-PadAC15)") (class "Default")
      (node (ref "U7") (pin "AC15") (pinfunction "IO_L16P_2_AC15") (pintype "passive"))
    )
    (net (code "103") (name "unconnected-(U7C-IO_L20N_2-PadAA15)") (class "Default")
      (node (ref "U7") (pin "AA15") (pinfunction "IO_L20N_2_AA15") (pintype "passive"))
    )
    (net (code "104") (name "unconnected-(U7C-IO_L29N_GCLK2_2-PadAF14)") (class "Default")
      (node (ref "U7") (pin "AF14") (pinfunction "IO_L29N_GCLK2_2_AF14") (pintype "passive"))
    )
    (net (code "105") (name "unconnected-(U7C-IO_L29P_GCLK3_2-PadAD14)") (class "Default")
      (node (ref "U7") (pin "AD14") (pinfunction "IO_L29P_GCLK3_2_AD14") (pintype "passive"))
    )
    (net (code "106") (name "unconnected-(U7C-IO_L31P_GCLK31_D14_2-PadAC13)") (class "Default")
      (node (ref "U7") (pin "AC13") (pinfunction "IO_L31P_GCLK31_D14_2_AC13") (pintype "passive"))
    )
    (net (code "107") (name "unconnected-(U8-NC-Pad1)") (class "Default")
      (node (ref "U8") (pin "1") (pinfunction "NC_1") (pintype "passive+no_connect"))
    )
    (net (code "108") (name "unconnected-(U9-NC-Pad1)") (class "Default")
      (node (ref "U9") (pin "1") (pinfunction "NC_1") (pintype "passive+no_connect"))
    )
  )
)
